# ApolloVoltReg.net
KiCad netlist of a schematic drawn in EAGLE
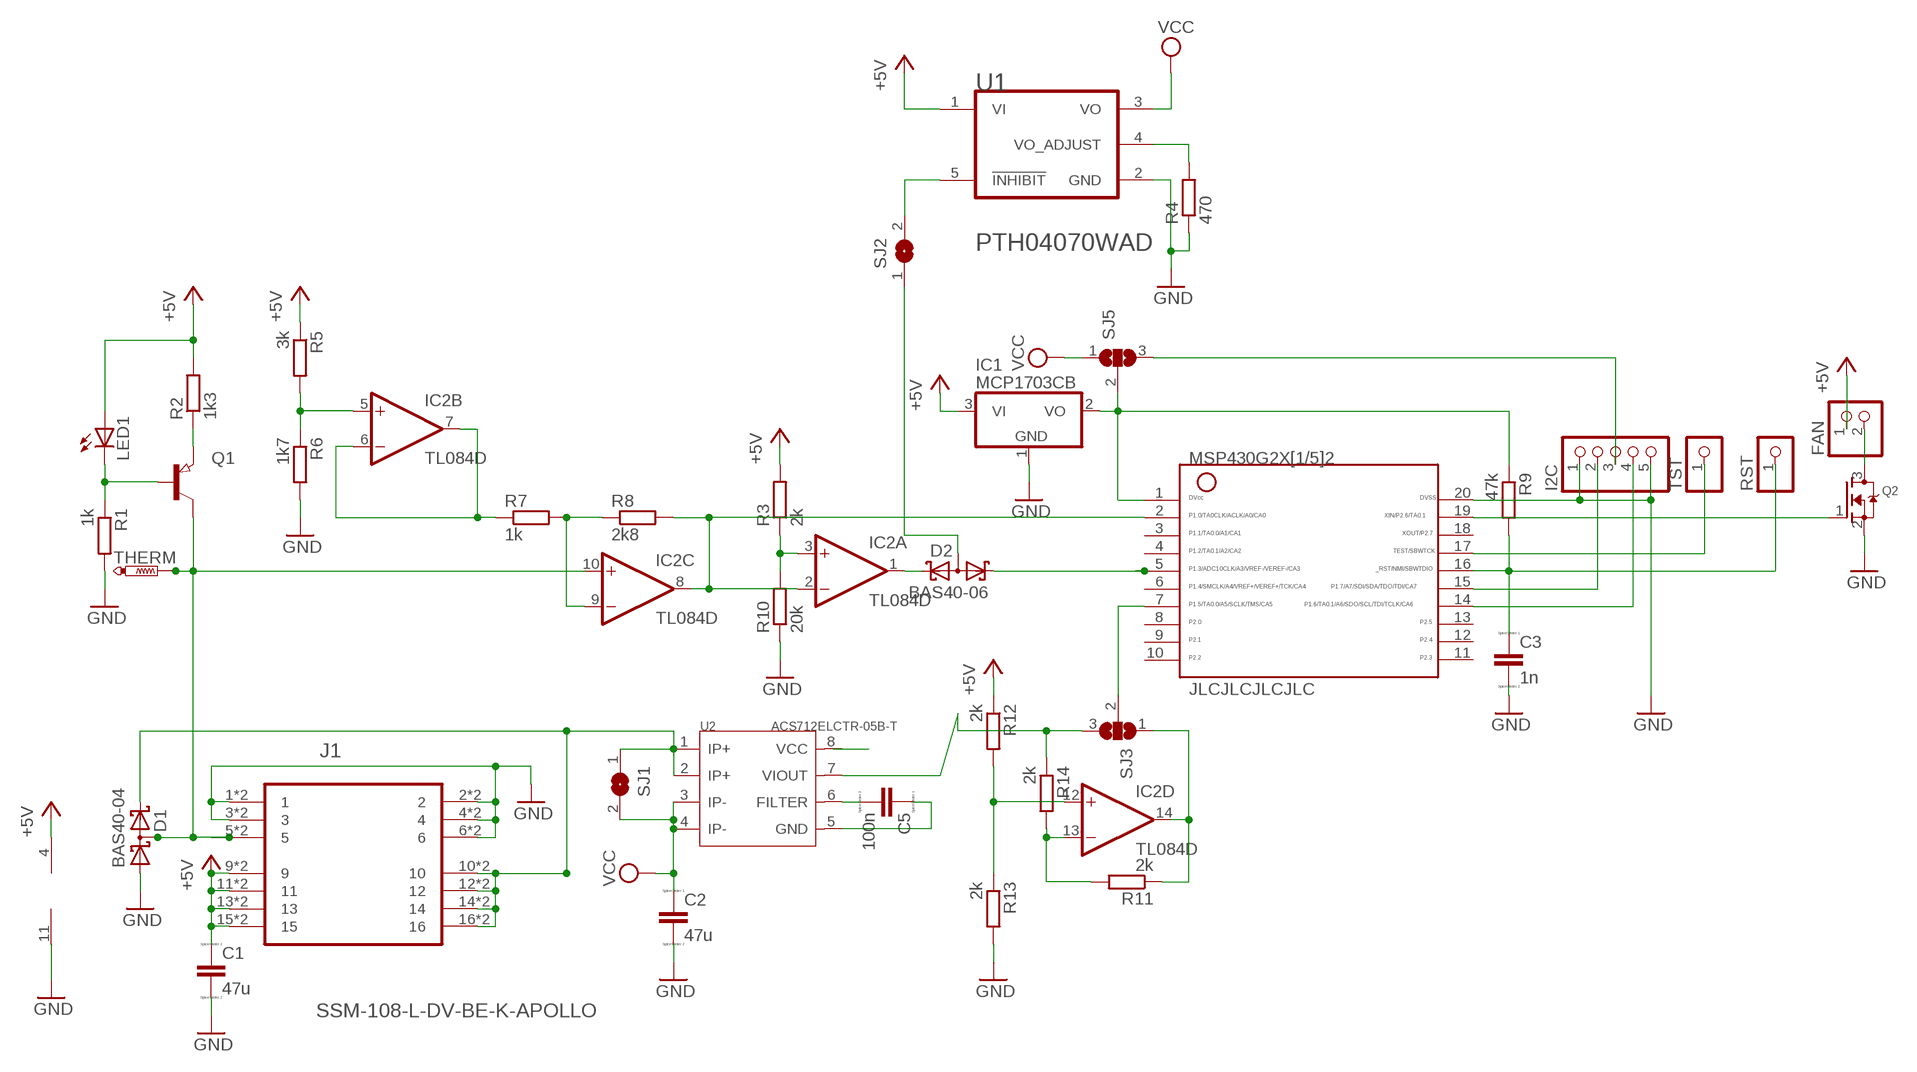
[diagram p0: schematic, sheet 1]

(export (version "E")
  (design (tool "Eeschema 10.0.6"))
  (components
    (comp (ref "C1")
      (value "47u")
      (footprint "eagle-import:C1210")
      (libsource (lib "eagle-import") (part "CC1210"))
    )
    (comp (ref "C2")
      (value "47u")
      (footprint "eagle-import:C1210")
      (libsource (lib "eagle-import") (part "CC1210"))
    )
    (comp (ref "C3")
      (value "1n")
      (footprint "eagle-import:C0603")
      (libsource (lib "eagle-import") (part "CC0603"))
    )
    (comp (ref "C5")
      (value "100n")
      (footprint "eagle-import:C0603")
      (libsource (lib "eagle-import") (part "CC0603"))
    )
    (comp (ref "D1")
      (value "BAS40-04")
      (footprint "eagle-import:SOT23")
      (libsource (lib "eagle-import") (part "BAS40-04"))
    )
    (comp (ref "D2")
      (value "BAS40-06")
      (footprint "eagle-import:SOT23")
      (libsource (lib "eagle-import") (part "BAS40-06"))
    )
    (comp (ref "FAN")
      (value "PINHD-1X2")
      (footprint "eagle-import:1X02")
      (libsource (lib "eagle-import") (part "PINHD-1X2"))
    )
    (comp (ref "I2C")
      (value "PINHD-1X5")
      (footprint "eagle-import:1X05")
      (libsource (lib "eagle-import") (part "PINHD-1X5"))
    )
    (comp (ref "IC1")
      (value "MCP1703CB")
      (footprint "eagle-import:SOT23")
      (libsource (lib "eagle-import") (part "MCP1703CB"))
    )
    (comp (ref "IC2")
      (value "TL084D")
      (footprint "eagle-import:SO14")
      (libsource (lib "eagle-import") (part "TL084D"))
    )
    (comp (ref "J1")
      (value "SSM-108-L-DV-BE-K-APOLLO")
      (footprint "eagle-import:SAMTEC_SSM-108-L-DV-BE-K-APOLLO")
      (libsource (lib "eagle-import") (part "SSM-108-L-DV-BE-K-APOLLO"))
    )
    (comp (ref "JLCJLCJLCJLC")
      (value "G2X[1/5]2---N20")
      (footprint "eagle-import:N20")
      (libsource (lib "eagle-import") (part "G2X[1/5]2---N20"))
    )
    (comp (ref "LED1")
      (value "LED3MM")
      (footprint "eagle-import:LED3MM")
      (libsource (lib "eagle-import") (part "LED3MM"))
    )
    (comp (ref "Q1")
      (value "PNP-TRANSISTOR_SOT23")
      (footprint "eagle-import:SOT23")
      (libsource (lib "eagle-import") (part "PNP-TRANSISTOR_SOT23"))
    )
    (comp (ref "Q2")
      (value "MOSFET-NREFLOW")
      (footprint "eagle-import:SOT23")
      (libsource (lib "eagle-import") (part "MOSFET-NREFLOW"))
    )
    (comp (ref "R1")
      (value "1k")
      (footprint "eagle-import:R0805")
      (libsource (lib "eagle-import") (part "R-EU_R0805"))
    )
    (comp (ref "R2")
      (value "1k3")
      (footprint "eagle-import:R0805")
      (libsource (lib "eagle-import") (part "R-EU_R0805"))
    )
    (comp (ref "R3")
      (value "2k")
      (footprint "eagle-import:R0805")
      (libsource (lib "eagle-import") (part "R-EU_R0805"))
    )
    (comp (ref "R4")
      (value "470")
      (footprint "eagle-import:R0805")
      (libsource (lib "eagle-import") (part "R-EU_R0805"))
    )
    (comp (ref "R5")
      (value "3k")
      (footprint "eagle-import:R0805")
      (libsource (lib "eagle-import") (part "R-EU_R0805"))
    )
    (comp (ref "R6")
      (value "1k7")
      (footprint "eagle-import:R0805")
      (libsource (lib "eagle-import") (part "R-EU_R0805"))
    )
    (comp (ref "R7")
      (value "1k")
      (footprint "eagle-import:R0805")
      (libsource (lib "eagle-import") (part "R-EU_R0805"))
    )
    (comp (ref "R8")
      (value "2k8")
      (footprint "eagle-import:R0805")
      (libsource (lib "eagle-import") (part "R-EU_R0805"))
    )
    (comp (ref "R9")
      (value "47k")
      (footprint "eagle-import:R0603")
      (libsource (lib "eagle-import") (part "R-EU_R0603"))
    )
    (comp (ref "R10")
      (value "20k")
      (footprint "eagle-import:R0805")
      (libsource (lib "eagle-import") (part "R-EU_R0805"))
    )
    (comp (ref "R11")
      (value "2k")
      (footprint "eagle-import:R0805")
      (libsource (lib "eagle-import") (part "R-EU_R0805"))
    )
    (comp (ref "R12")
      (value "2k")
      (footprint "eagle-import:R0805")
      (libsource (lib "eagle-import") (part "R-EU_R0805"))
    )
    (comp (ref "R13")
      (value "2k")
      (footprint "eagle-import:R0805")
      (libsource (lib "eagle-import") (part "R-EU_R0805"))
    )
    (comp (ref "R14")
      (value "2k")
      (footprint "eagle-import:R0603")
      (libsource (lib "eagle-import") (part "R-EU_R0603"))
    )
    (comp (ref "RST")
      (value "PINHD-1X1CB")
      (footprint "eagle-import:1X01-CLEANBIG")
      (libsource (lib "eagle-import") (part "PINHD-1X1CB"))
    )
    (comp (ref "SJ1")
      (value "SJW")
      (footprint "eagle-import:SJW")
      (libsource (lib "eagle-import") (part "SJW"))
    )
    (comp (ref "SJ2") (value "SJ") (footprint "eagle-import:SJ") (libsource (lib "eagle-import") (part "SJ")))
    (comp (ref "SJ3")
      (value "SJ2W")
      (footprint "eagle-import:SJ_2")
      (libsource (lib "eagle-import") (part "SJ2W"))
    )
    (comp (ref "SJ5")
      (value "SJ2W")
      (footprint "eagle-import:SJ_2")
      (libsource (lib "eagle-import") (part "SJ2W"))
    )
    (comp (ref "THERM")
      (value "PTR1B1,27")
      (footprint "eagle-import:B1,27")
      (libsource (lib "eagle-import") (part "PTR1B1,27"))
    )
    (comp (ref "TST")
      (value "PINHD-1X1CB")
      (footprint "eagle-import:1X01-CLEANBIG")
      (libsource (lib "eagle-import") (part "PINHD-1X1CB"))
    )
    (comp (ref "U1")
      (value "TEXAS_INSTRUMENTS_PTH04070WADTEXAS_INSTRUMENTS_PTH04070WAD_0_0")
      (footprint "eagle-import:TEXAS_INSTRUMENTS_PTH04070WAD_0")
      (fields (field (name "MF") "Texas Instruments") (field (name "MPN") "PTH04070WAD"))
      (libsource (lib "eagle-import") (part "TEXAS_INSTRUMENTS_PTH04070WADTEXAS_INSTRUMENTS_PTH04070WAD_0_0"))
    )
    (comp (ref "U2")
      (value "ACS712ELCTR-05B-T")
      (footprint "eagle-import:SOIC8-1.27-5X4MM")
      (libsource (lib "eagle-import") (part "CURRENT-ACS712ELCTR-05B-T(SOIC8-5X4MM)"))
    )
  )
  (nets
    (net (code "1") (name "+5V") (class "Default")
      (node (ref "C1") (pin "1") (pinfunction "1_1") (pintype "passive"))
      (node (ref "FAN") (pin "1") (pinfunction "1_1") (pintype "passive"))
      (node (ref "IC1") (pin "3") (pinfunction "VI_3") (pintype "input"))
      (node (ref "IC2") (pin "4") (pinfunction "V+_4") (pintype "power_in"))
      (node (ref "J1") (pin "11") (pinfunction "11_11") (pintype "passive"))
      (node (ref "J1") (pin "13") (pinfunction "13_13") (pintype "passive"))
      (node (ref "J1") (pin "15") (pinfunction "15_15") (pintype "passive"))
      (node (ref "J1") (pin "29") (pinfunction "9_29") (pintype "passive"))
      (node (ref "J1") (pin "31") (pinfunction "11_31") (pintype "passive"))
      (node (ref "J1") (pin "33") (pinfunction "13_33") (pintype "passive"))
      (node (ref "J1") (pin "35") (pinfunction "15_35") (pintype "passive"))
      (node (ref "J1") (pin "9") (pinfunction "9_9") (pintype "passive"))
      (node (ref "LED1") (pin "A") (pinfunction "A_A") (pintype "passive"))
      (node (ref "R12") (pin "1") (pinfunction "1_1") (pintype "passive"))
      (node (ref "R2") (pin "2") (pinfunction "2_2") (pintype "passive"))
      (node (ref "R3") (pin "2") (pinfunction "2_2") (pintype "passive"))
      (node (ref "R5") (pin "1") (pinfunction "1_1") (pintype "passive"))
      (node (ref "U1") (pin "1") (pinfunction "VI_1") (pintype "power_in"))
      (node (ref "U2") (pin "8") (pinfunction "VCC_8") (pintype "bidirectional"))
    )
    (net (code "2") (name "/ACS_OUT") (class "Default")
      (node (ref "R14") (pin "1") (pinfunction "1_1") (pintype "passive"))
      (node (ref "SJ3") (pin "3") (pinfunction "3_3") (pintype "passive"))
      (node (ref "U2") (pin "7") (pinfunction "VIOUT_7") (pintype "bidirectional"))
    )
    (net (code "3") (name "GND") (class "Default")
      (node (ref "C1") (pin "2") (pinfunction "2_2") (pintype "passive"))
      (node (ref "C2") (pin "2") (pinfunction "2_2") (pintype "passive"))
      (node (ref "C3") (pin "2") (pinfunction "2_2") (pintype "passive"))
      (node (ref "C5") (pin "1") (pinfunction "1_1") (pintype "passive"))
      (node (ref "D1") (pin "1") (pinfunction "A1_1") (pintype "passive"))
      (node (ref "I2C") (pin "1") (pinfunction "1_1") (pintype "passive"))
      (node (ref "I2C") (pin "5") (pinfunction "5_5") (pintype "passive"))
      (node (ref "IC1") (pin "1") (pinfunction "GND_1") (pintype "passive"))
      (node (ref "IC2") (pin "11") (pinfunction "V-_11") (pintype "power_in"))
      (node (ref "J1") (pin "1") (pinfunction "1_1") (pintype "passive"))
      (node (ref "J1") (pin "2") (pinfunction "2_2") (pintype "passive"))
      (node (ref "J1") (pin "21") (pinfunction "1_21") (pintype "passive"))
      (node (ref "J1") (pin "22") (pinfunction "2_22") (pintype "passive"))
      (node (ref "J1") (pin "23") (pinfunction "3_23") (pintype "passive"))
      (node (ref "J1") (pin "24") (pinfunction "4_24") (pintype "passive"))
      (node (ref "J1") (pin "26") (pinfunction "6_26") (pintype "passive"))
      (node (ref "J1") (pin "3") (pinfunction "3_3") (pintype "passive"))
      (node (ref "J1") (pin "4") (pinfunction "4_4") (pintype "passive"))
      (node (ref "J1") (pin "6") (pinfunction "6_6") (pintype "passive"))
      (node (ref "JLCJLCJLCJLC") (pin "20") (pinfunction "20_20") (pintype "bidirectional"))
      (node (ref "Q2") (pin "2") (pinfunction "S_2") (pintype "bidirectional"))
      (node (ref "R1") (pin "2") (pinfunction "2_2") (pintype "passive"))
      (node (ref "R10") (pin "1") (pinfunction "1_1") (pintype "passive"))
      (node (ref "R13") (pin "2") (pinfunction "2_2") (pintype "passive"))
      (node (ref "R4") (pin "1") (pinfunction "1_1") (pintype "passive"))
      (node (ref "R6") (pin "2") (pinfunction "2_2") (pintype "passive"))
      (node (ref "U1") (pin "2") (pinfunction "GND_2") (pintype "power_in"))
      (node (ref "U2") (pin "5") (pinfunction "GND_5") (pintype "bidirectional"))
    )
    (net (code "4") (name "Net-(C3-Pad1)") (class "Default")
      (node (ref "C3") (pin "1") (pinfunction "1_1") (pintype "passive"))
      (node (ref "JLCJLCJLCJLC") (pin "16") (pinfunction "16_16") (pintype "bidirectional"))
      (node (ref "R9") (pin "2") (pinfunction "2_2") (pintype "passive"))
      (node (ref "RST") (pin "1") (pinfunction "1_1") (pintype "passive"))
    )
    (net (code "5") (name "Net-(D1-C1A2)") (class "Default")
      (node (ref "D1") (pin "3") (pinfunction "C1A2_3") (pintype "passive"))
      (node (ref "IC2") (pin "10") (pinfunction "+IN_10") (pintype "input"))
      (node (ref "J1") (pin "25") (pinfunction "5_25") (pintype "passive"))
      (node (ref "J1") (pin "5") (pinfunction "5_5") (pintype "passive"))
      (node (ref "Q1") (pin "3") (pinfunction "C_3") (pintype "passive"))
      (node (ref "THERM") (pin "TP") (pinfunction "TP_TP") (pintype "input"))
    )
    (net (code "6") (name "Net-(D1-C2)") (class "Default")
      (node (ref "D1") (pin "2") (pinfunction "C2_2") (pintype "passive"))
      (node (ref "J1") (pin "10") (pinfunction "10_10") (pintype "passive"))
      (node (ref "J1") (pin "12") (pinfunction "12_12") (pintype "passive"))
      (node (ref "J1") (pin "14") (pinfunction "14_14") (pintype "passive"))
      (node (ref "J1") (pin "16") (pinfunction "16_16") (pintype "passive"))
      (node (ref "J1") (pin "30") (pinfunction "10_30") (pintype "passive"))
      (node (ref "J1") (pin "32") (pinfunction "12_32") (pintype "passive"))
      (node (ref "J1") (pin "34") (pinfunction "14_34") (pintype "passive"))
      (node (ref "J1") (pin "36") (pinfunction "16_36") (pintype "passive"))
      (node (ref "SJ1") (pin "1") (pinfunction "1_1") (pintype "passive"))
      (node (ref "U2") (pin "1") (pinfunction "IP+_1") (pintype "bidirectional"))
      (node (ref "U2") (pin "2") (pinfunction "IP+_2") (pintype "bidirectional"))
    )
    (net (code "7") (name "Net-(D2-AA)") (class "Default")
      (node (ref "D2") (pin "3") (pinfunction "AA_3") (pintype "passive"))
      (node (ref "SJ2") (pin "1") (pinfunction "1_1") (pintype "passive"))
    )
    (net (code "8") (name "Net-(D2-K1)") (class "Default")
      (node (ref "D2") (pin "1") (pinfunction "K1_1") (pintype "passive"))
      (node (ref "JLCJLCJLCJLC") (pin "5") (pinfunction "5_5") (pintype "bidirectional"))
    )
    (net (code "9") (name "Net-(D2-K2)") (class "Default")
      (node (ref "D2") (pin "2") (pinfunction "K2_2") (pintype "passive"))
      (node (ref "IC2") (pin "1") (pinfunction "OUT_1") (pintype "output"))
    )
    (net (code "10") (name "Net-(I2C-Pad2)") (class "Default")
      (node (ref "I2C") (pin "2") (pinfunction "2_2") (pintype "passive"))
      (node (ref "JLCJLCJLCJLC") (pin "15") (pinfunction "15_15") (pintype "bidirectional"))
    )
    (net (code "11") (name "Net-(I2C-Pad3)") (class "Default")
      (node (ref "I2C") (pin "3") (pinfunction "3_3") (pintype "passive"))
      (node (ref "SJ5") (pin "3") (pinfunction "3_3") (pintype "passive"))
    )
    (net (code "12") (name "Net-(I2C-Pad4)") (class "Default")
      (node (ref "I2C") (pin "4") (pinfunction "4_4") (pintype "passive"))
      (node (ref "JLCJLCJLCJLC") (pin "14") (pinfunction "14_14") (pintype "bidirectional"))
    )
    (net (code "13") (name "Net-(IC1-VO)") (class "Default")
      (node (ref "IC1") (pin "2") (pinfunction "VO_2") (pintype "passive"))
      (node (ref "JLCJLCJLCJLC") (pin "1") (pinfunction "1_1") (pintype "bidirectional"))
      (node (ref "R9") (pin "1") (pinfunction "1_1") (pintype "passive"))
      (node (ref "SJ5") (pin "2") (pinfunction "2_2") (pintype "passive"))
    )
    (net (code "14") (name "Net-(IC2A-+IN)") (class "Default")
      (node (ref "IC2") (pin "3") (pinfunction "+IN_3") (pintype "input"))
      (node (ref "R10") (pin "2") (pinfunction "2_2") (pintype "passive"))
      (node (ref "R3") (pin "1") (pinfunction "1_1") (pintype "passive"))
    )
    (net (code "15") (name "Net-(IC2A--IN)") (class "Default")
      (node (ref "IC2") (pin "2") (pinfunction "-IN_2") (pintype "input"))
      (node (ref "IC2") (pin "8") (pinfunction "OUT_8") (pintype "output"))
      (node (ref "JLCJLCJLCJLC") (pin "2") (pinfunction "2_2") (pintype "bidirectional"))
      (node (ref "R8") (pin "2") (pinfunction "2_2") (pintype "passive"))
    )
    (net (code "16") (name "Net-(IC2B-+IN)") (class "Default")
      (node (ref "IC2") (pin "5") (pinfunction "+IN_5") (pintype "input"))
      (node (ref "R5") (pin "2") (pinfunction "2_2") (pintype "passive"))
      (node (ref "R6") (pin "1") (pinfunction "1_1") (pintype "passive"))
    )
    (net (code "17") (name "Net-(IC2B--IN)") (class "Default")
      (node (ref "IC2") (pin "6") (pinfunction "-IN_6") (pintype "input"))
      (node (ref "IC2") (pin "7") (pinfunction "OUT_7") (pintype "output"))
      (node (ref "R7") (pin "1") (pinfunction "1_1") (pintype "passive"))
    )
    (net (code "18") (name "Net-(IC2C--IN)") (class "Default")
      (node (ref "IC2") (pin "9") (pinfunction "-IN_9") (pintype "input"))
      (node (ref "R7") (pin "2") (pinfunction "2_2") (pintype "passive"))
      (node (ref "R8") (pin "1") (pinfunction "1_1") (pintype "passive"))
    )
    (net (code "19") (name "Net-(IC2D-+IN)") (class "Default")
      (node (ref "IC2") (pin "12") (pinfunction "+IN_12") (pintype "input"))
      (node (ref "R12") (pin "2") (pinfunction "2_2") (pintype "passive"))
      (node (ref "R13") (pin "1") (pinfunction "1_1") (pintype "passive"))
    )
    (net (code "20") (name "Net-(IC2D--IN)") (class "Default")
      (node (ref "IC2") (pin "13") (pinfunction "-IN_13") (pintype "input"))
      (node (ref "R11") (pin "2") (pinfunction "2_2") (pintype "passive"))
      (node (ref "R14") (pin "2") (pinfunction "2_2") (pintype "passive"))
    )
    (net (code "21") (name "Net-(IC2D-OUT)") (class "Default")
      (node (ref "IC2") (pin "14") (pinfunction "OUT_14") (pintype "output"))
      (node (ref "R11") (pin "1") (pinfunction "1_1") (pintype "passive"))
      (node (ref "SJ3") (pin "1") (pinfunction "1_1") (pintype "passive"))
    )
    (net (code "22") (name "Net-(JLCJLCJLCJLC-Pad7)") (class "Default")
      (node (ref "JLCJLCJLCJLC") (pin "7") (pinfunction "7_7") (pintype "bidirectional"))
      (node (ref "SJ3") (pin "2") (pinfunction "2_2") (pintype "passive"))
    )
    (net (code "23") (name "Net-(JLCJLCJLCJLC-Pad17)") (class "Default")
      (node (ref "JLCJLCJLCJLC") (pin "17") (pinfunction "17_17") (pintype "bidirectional"))
      (node (ref "TST") (pin "1") (pinfunction "1_1") (pintype "passive"))
    )
    (net (code "24") (name "Net-(LED1-C)") (class "Default")
      (node (ref "LED1") (pin "K") (pinfunction "C_K") (pintype "passive"))
      (node (ref "Q1") (pin "1") (pinfunction "B_1") (pintype "passive"))
      (node (ref "R1") (pin "1") (pinfunction "1_1") (pintype "passive"))
    )
    (net (code "25") (name "Net-(Q1-E)") (class "Default")
      (node (ref "Q1") (pin "2") (pinfunction "E_2") (pintype "passive"))
      (node (ref "R2") (pin "1") (pinfunction "1_1") (pintype "passive"))
    )
    (net (code "26") (name "Net-(Q2-D)") (class "Default")
      (node (ref "FAN") (pin "2") (pinfunction "2_2") (pintype "passive"))
      (node (ref "Q2") (pin "3") (pinfunction "D_3") (pintype "bidirectional"))
    )
    (net (code "27") (name "Net-(Q2-G)") (class "Default")
      (node (ref "JLCJLCJLCJLC") (pin "19") (pinfunction "19_19") (pintype "bidirectional"))
      (node (ref "Q2") (pin "1") (pinfunction "G_1") (pintype "bidirectional"))
    )
    (net (code "28") (name "Net-(U1-VO_ADJUST)") (class "Default")
      (node (ref "R4") (pin "2") (pinfunction "2_2") (pintype "passive"))
      (node (ref "U1") (pin "4") (pinfunction "VO_ADJUST_4") (pintype "input"))
    )
    (net (code "29") (name "Net-(U1-~{INHIBIT})") (class "Default")
      (node (ref "SJ2") (pin "2") (pinfunction "2_2") (pintype "passive"))
      (node (ref "U1") (pin "5") (pinfunction "~{INHIBIT}_5") (pintype "input"))
    )
    (net (code "30") (name "Net-(U2-FILTER)") (class "Default")
      (node (ref "C5") (pin "2") (pinfunction "2_2") (pintype "passive"))
      (node (ref "U2") (pin "6") (pinfunction "FILTER_6") (pintype "bidirectional"))
    )
    (net (code "31") (name "VCC") (class "Default")
      (node (ref "C2") (pin "1") (pinfunction "1_1") (pintype "passive"))
      (node (ref "SJ1") (pin "2") (pinfunction "2_2") (pintype "passive"))
      (node (ref "SJ5") (pin "1") (pinfunction "1_1") (pintype "passive"))
      (node (ref "U1") (pin "3") (pinfunction "VO_3") (pintype "power_in"))
      (node (ref "U2") (pin "3") (pinfunction "IP-_3") (pintype "bidirectional"))
      (node (ref "U2") (pin "4") (pinfunction "IP-_4") (pintype "bidirectional"))
    )
    (net (code "32") (name "unconnected-(JLCJLCJLCJLC-Pad3)") (class "Default")
      (node (ref "JLCJLCJLCJLC") (pin "3") (pinfunction "3_3") (pintype "bidirectional"))
    )
    (net (code "33") (name "unconnected-(JLCJLCJLCJLC-Pad4)") (class "Default")
      (node (ref "JLCJLCJLCJLC") (pin "4") (pinfunction "4_4") (pintype "bidirectional"))
    )
    (net (code "34") (name "unconnected-(JLCJLCJLCJLC-Pad6)") (class "Default")
      (node (ref "JLCJLCJLCJLC") (pin "6") (pinfunction "6_6") (pintype "bidirectional"))
    )
    (net (code "35") (name "unconnected-(JLCJLCJLCJLC-Pad8)") (class "Default")
      (node (ref "JLCJLCJLCJLC") (pin "8") (pinfunction "8_8") (pintype "bidirectional"))
    )
    (net (code "36") (name "unconnected-(JLCJLCJLCJLC-Pad9)") (class "Default")
      (node (ref "JLCJLCJLCJLC") (pin "9") (pinfunction "9_9") (pintype "bidirectional"))
    )
    (net (code "37") (name "unconnected-(JLCJLCJLCJLC-Pad10)") (class "Default")
      (node (ref "JLCJLCJLCJLC") (pin "10") (pinfunction "10_10") (pintype "bidirectional"))
    )
    (net (code "38") (name "unconnected-(JLCJLCJLCJLC-Pad11)") (class "Default")
      (node (ref "JLCJLCJLCJLC") (pin "11") (pinfunction "11_11") (pintype "bidirectional"))
    )
    (net (code "39") (name "unconnected-(JLCJLCJLCJLC-Pad12)") (class "Default")
      (node (ref "JLCJLCJLCJLC") (pin "12") (pinfunction "12_12") (pintype "bidirectional"))
    )
    (net (code "40") (name "unconnected-(JLCJLCJLCJLC-Pad13)") (class "Default")
      (node (ref "JLCJLCJLCJLC") (pin "13") (pinfunction "13_13") (pintype "bidirectional"))
    )
    (net (code "41") (name "unconnected-(JLCJLCJLCJLC-Pad18)") (class "Default")
      (node (ref "JLCJLCJLCJLC") (pin "18") (pinfunction "18_18") (pintype "bidirectional"))
    )
  )
)
